# AD9959.net
KiCad netlist of a schematic drawn in Altium Designer
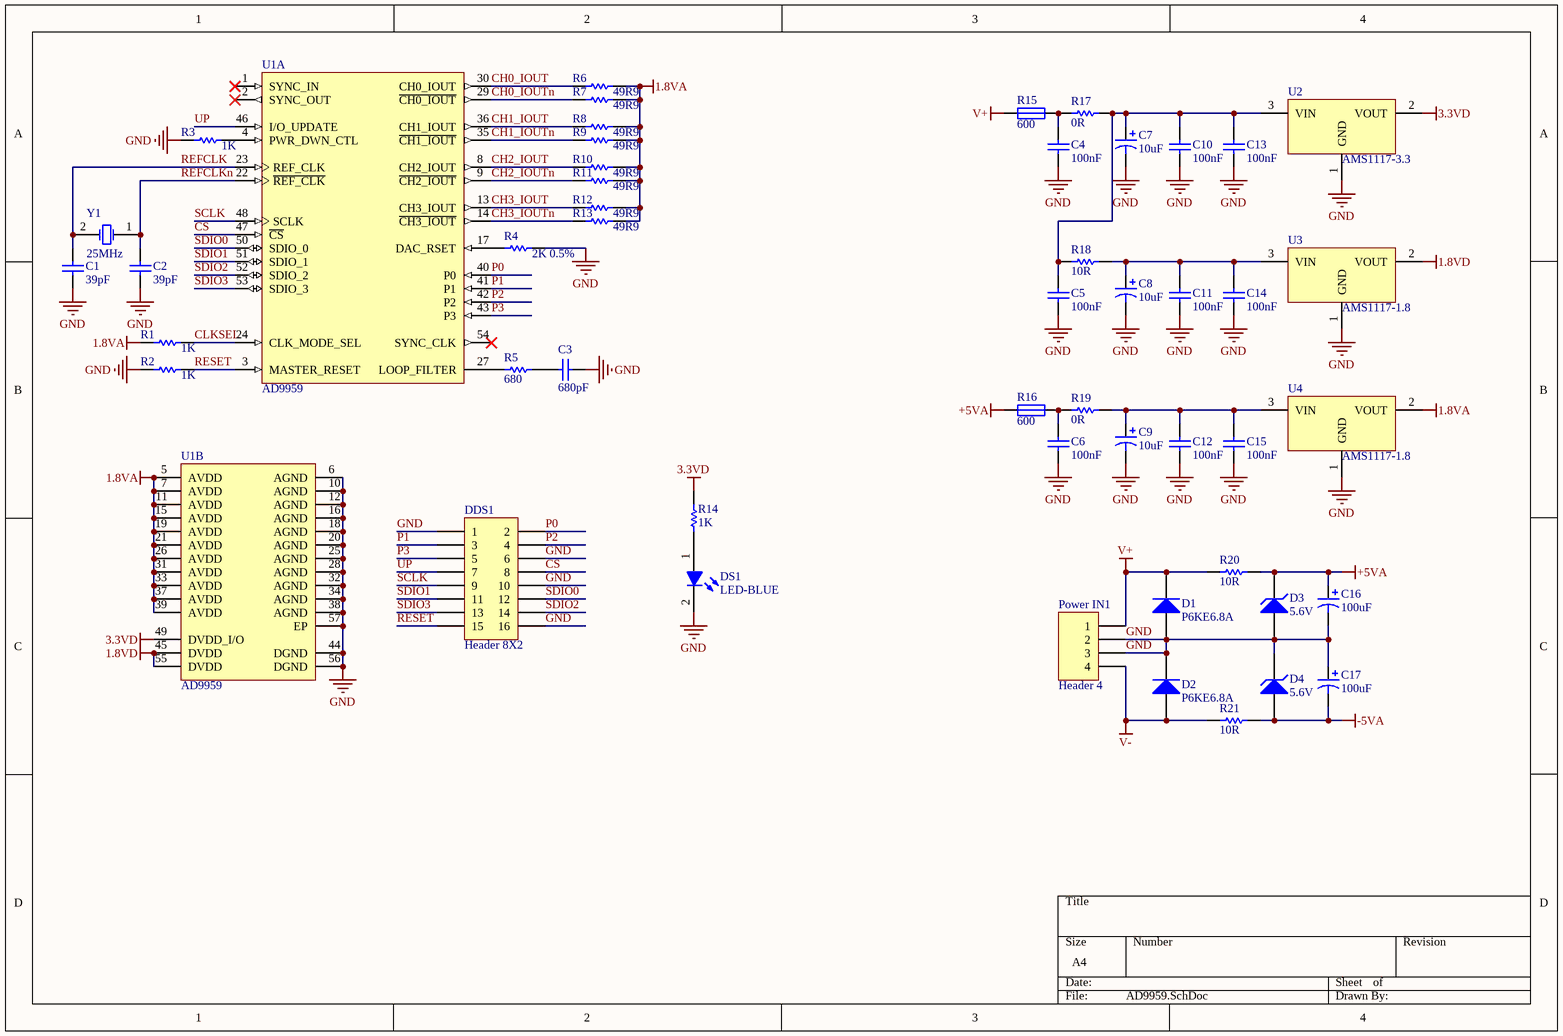
[diagram p0: AD9959.SchDoc]

(export (version "E")
  (design (tool "Eeschema 10.0.6"))
  (components
    (comp (ref "C1")
      (value "39pF")
      (footprint "CAPC0603(1608)55_M")
      (libsource (lib "Slivy's ibrary") (part "CAP"))
    )
    (comp (ref "C2")
      (value "39pF")
      (footprint "CAPC0603(1608)55_M")
      (libsource (lib "Slivy's ibrary") (part "CAP"))
    )
    (comp (ref "C3")
      (value "680pF")
      (footprint "CAPC0603(1608)55_M")
      (libsource (lib "Slivy's ibrary") (part "CAP"))
    )
    (comp (ref "C4")
      (value "100nF")
      (footprint "CAPC0603(1608)55_M")
      (libsource (lib "Slivy's ibrary") (part "CAP"))
    )
    (comp (ref "C5")
      (value "100nF")
      (footprint "CAPC0603(1608)55_M")
      (libsource (lib "Slivy's ibrary") (part "CAP"))
    )
    (comp (ref "C6")
      (value "100nF")
      (footprint "CAPC0603(1608)55_M")
      (libsource (lib "Slivy's ibrary") (part "CAP"))
    )
    (comp (ref "C7")
      (value "10uF")
      (footprint "CAPC3528")
      (libsource (lib "Slivy's ibrary") (part "CAP-Pol"))
    )
    (comp (ref "C8")
      (value "10uF")
      (footprint "CAPC3528")
      (libsource (lib "Slivy's ibrary") (part "CAP-Pol"))
    )
    (comp (ref "C9")
      (value "10uF")
      (footprint "CAPC3528")
      (libsource (lib "Slivy's ibrary") (part "CAP-Pol"))
    )
    (comp (ref "C10")
      (value "100nF")
      (footprint "CAPC0603(1608)55_M")
      (libsource (lib "Slivy's ibrary") (part "CAP"))
    )
    (comp (ref "C11")
      (value "100nF")
      (footprint "CAPC0603(1608)55_M")
      (libsource (lib "Slivy's ibrary") (part "CAP"))
    )
    (comp (ref "C12")
      (value "100nF")
      (footprint "CAPC0603(1608)55_M")
      (libsource (lib "Slivy's ibrary") (part "CAP"))
    )
    (comp (ref "C13")
      (value "100nF")
      (footprint "CAPC0603(1608)55_M")
      (libsource (lib "Slivy's ibrary") (part "CAP"))
    )
    (comp (ref "C14")
      (value "100nF")
      (footprint "CAPC0603(1608)55_M")
      (libsource (lib "Slivy's ibrary") (part "CAP"))
    )
    (comp (ref "C15")
      (value "100nF")
      (footprint "CAPC0603(1608)55_M")
      (libsource (lib "Slivy's ibrary") (part "CAP"))
    )
    (comp (ref "C16")
      (value "100uF")
      (footprint "CAPC7343")
      (libsource (lib "Slivy's ibrary") (part "CAP-Pol"))
    )
    (comp (ref "C17")
      (value "100uF")
      (footprint "CAPC7343")
      (libsource (lib "Slivy's ibrary") (part "CAP-Pol"))
    )
    (comp (ref "D1")
      (value "P6KE6.8A")
      (footprint "DO-214AC")
      (libsource (lib "Slivy's ibrary") (part "Diode"))
    )
    (comp (ref "D2")
      (value "P6KE6.8A")
      (footprint "DO-214AC")
      (libsource (lib "Slivy's ibrary") (part "Diode"))
    )
    (comp (ref "D3")
      (value "5.6V")
      (footprint "LL34")
      (description "Zener Diode")
      (fields (field (name "PUBLISHER") "Altium Limited"))
      (libsource (lib "Miscellaneous Devices") (part "D Zener"))
    )
    (comp (ref "D4")
      (value "5.6V")
      (footprint "LL34")
      (description "Zener Diode")
      (fields (field (name "PUBLISHER") "Altium Limited"))
      (libsource (lib "Miscellaneous Devices") (part "D Zener"))
    )
    (comp (ref "DDS1")
      (value "Header 8X2")
      (footprint "HEADER8X2")
      (description "Header, 8-Pin, Dual row")
      (fields (field (name "PUBLISHER") "Altium Limited"))
      (libsource (lib "Miscellaneous Connectors") (part "Header 8X2"))
    )
    (comp (ref "DS1")
      (value "LED-BLUE")
      (footprint "0603LED_BLUE_V")
      (libsource (lib "Slivy's ibrary") (part "LED-BLUE"))
    )
    (comp (ref "Power IN1")
      (value "Header 4")
      (footprint "3.96-4")
      (description "Header, 4-Pin")
      (fields (field (name "PUBLISHER") "Altium Limited"))
      (libsource (lib "Miscellaneous Connectors") (part "Header 4"))
    )
    (comp (ref "R1")
      (value "1K")
      (footprint "RESC0603(1608)_M")
      (libsource (lib "Slivy's ibrary") (part "RES"))
    )
    (comp (ref "R2")
      (value "1K")
      (footprint "RESC0603(1608)_M")
      (libsource (lib "Slivy's ibrary") (part "RES"))
    )
    (comp (ref "R3")
      (value "1K")
      (footprint "RESC0603(1608)_M")
      (libsource (lib "Slivy's ibrary") (part "RES"))
    )
    (comp (ref "R4")
      (value "2K 0.5%")
      (footprint "RESC0603(1608)_M")
      (libsource (lib "Slivy's ibrary") (part "RES"))
    )
    (comp (ref "R5")
      (value "680")
      (footprint "RESC0603(1608)_M")
      (libsource (lib "Slivy's ibrary") (part "RES"))
    )
    (comp (ref "R6")
      (value "49R9")
      (footprint "RESC0603(1608)_M")
      (libsource (lib "Slivy's ibrary") (part "RES"))
    )
    (comp (ref "R7")
      (value "49R9")
      (footprint "RESC0603(1608)_M")
      (libsource (lib "Slivy's ibrary") (part "RES"))
    )
    (comp (ref "R8")
      (value "49R9")
      (footprint "RESC0603(1608)_M")
      (libsource (lib "Slivy's ibrary") (part "RES"))
    )
    (comp (ref "R9")
      (value "49R9")
      (footprint "RESC0603(1608)_M")
      (libsource (lib "Slivy's ibrary") (part "RES"))
    )
    (comp (ref "R10")
      (value "49R9")
      (footprint "RESC0603(1608)_M")
      (libsource (lib "Slivy's ibrary") (part "RES"))
    )
    (comp (ref "R11")
      (value "49R9")
      (footprint "RESC0603(1608)_M")
      (libsource (lib "Slivy's ibrary") (part "RES"))
    )
    (comp (ref "R12")
      (value "49R9")
      (footprint "RESC0603(1608)_M")
      (libsource (lib "Slivy's ibrary") (part "RES"))
    )
    (comp (ref "R13")
      (value "49R9")
      (footprint "RESC0603(1608)_M")
      (libsource (lib "Slivy's ibrary") (part "RES"))
    )
    (comp (ref "R14")
      (value "1K")
      (footprint "RESC0603(1608)_M")
      (libsource (lib "Slivy's ibrary") (part "RES"))
    )
    (comp (ref "R15")
      (value "600")
      (footprint "SMD1206")
      (description "Ferrite Bead")
      (fields
        (field (name "MANUFACTURER") "Generic Components")
        (field (name "PUBLISHER") "Altium Hobart Technology Centre")
      )
      (libsource (lib "Integrated_Library1") (part "Ferrite Bead"))
    )
    (comp (ref "R16")
      (value "600")
      (footprint "SMD1206")
      (description "Ferrite Bead")
      (fields
        (field (name "MANUFACTURER") "Generic Components")
        (field (name "PUBLISHER") "Altium Hobart Technology Centre")
      )
      (libsource (lib "Integrated_Library1") (part "Ferrite Bead"))
    )
    (comp (ref "R17")
      (value "0R")
      (footprint "RESC0603(1608)_M")
      (libsource (lib "Slivy's ibrary") (part "RES"))
    )
    (comp (ref "R18")
      (value "10R")
      (footprint "RESC0603(1608)_M")
      (libsource (lib "Slivy's ibrary") (part "RES"))
    )
    (comp (ref "R19")
      (value "0R")
      (footprint "RESC0603(1608)_M")
      (libsource (lib "Slivy's ibrary") (part "RES"))
    )
    (comp (ref "R20")
      (value "10R")
      (footprint "RESC0603(1608)_M")
      (libsource (lib "Slivy's ibrary") (part "RES"))
    )
    (comp (ref "R21")
      (value "10R")
      (footprint "RESC0603(1608)_M")
      (libsource (lib "Slivy's ibrary") (part "RES"))
    )
    (comp (ref "U1") (value "AD9959") (footprint "QFN56") (libsource (lib "Slivy's ibrary") (part "AD9959")))
    (comp (ref "U2")
      (value "AMS1117-3.3")
      (footprint "SOT-223_M")
      (libsource (lib "Slivy's ibrary") (part "AMS1117"))
    )
    (comp (ref "U3")
      (value "AMS1117-1.8")
      (footprint "SOT-223_M")
      (libsource (lib "Slivy's ibrary") (part "AMS1117"))
    )
    (comp (ref "U4")
      (value "AMS1117-1.8")
      (footprint "SOT-223_M")
      (libsource (lib "Slivy's ibrary") (part "AMS1117"))
    )
    (comp (ref "Y1")
      (value "25MHz")
      (footprint "HC-49S")
      (description "Crystal Oscillator")
      (fields (field (name "PUBLISHER") "Altium Limited"))
      (libsource (lib "Slivy's ibrary") (part "XTAL"))
    )
  )
  (nets
    (net (code "1") (name "+5VA") (class "Default")
      (node (ref "C16") (pin "1") (pinfunction "1_1") (pintype "passive"))
      (node (ref "D3") (pin "2") (pinfunction "K_2") (pintype "passive"))
      (node (ref "R16") (pin "1") (pinfunction "1_1") (pintype "passive"))
      (node (ref "R20") (pin "2") (pinfunction "2_2") (pintype "passive"))
    )
    (net (code "2") (name "-5VA") (class "Default")
      (node (ref "C17") (pin "2") (pinfunction "2_2") (pintype "passive"))
      (node (ref "D4") (pin "1") (pinfunction "A_1") (pintype "passive"))
      (node (ref "R21") (pin "2") (pinfunction "2_2") (pintype "passive"))
    )
    (net (code "3") (name "/CH0_IOUT") (class "Default")
      (node (ref "R6") (pin "1") (pinfunction "1_1") (pintype "passive"))
      (node (ref "U1") (pin "30") (pinfunction "CH0_IOUT_30") (pintype "output"))
    )
    (net (code "4") (name "/CH0_IOUTn") (class "Default")
      (node (ref "R7") (pin "1") (pinfunction "1_1") (pintype "passive"))
      (node (ref "U1") (pin "29") (pinfunction "~{CH0_IOUT}_29") (pintype "output"))
    )
    (net (code "5") (name "/CH1_IOUT") (class "Default")
      (node (ref "R8") (pin "1") (pinfunction "1_1") (pintype "passive"))
      (node (ref "U1") (pin "36") (pinfunction "CH1_IOUT_36") (pintype "output"))
    )
    (net (code "6") (name "/CH1_IOUTn") (class "Default")
      (node (ref "R9") (pin "1") (pinfunction "1_1") (pintype "passive"))
      (node (ref "U1") (pin "35") (pinfunction "~{CH1_IOUT}_35") (pintype "output"))
    )
    (net (code "7") (name "/CH2_IOUT") (class "Default")
      (node (ref "R10") (pin "1") (pinfunction "1_1") (pintype "passive"))
      (node (ref "U1") (pin "8") (pinfunction "CH2_IOUT_8") (pintype "output"))
    )
    (net (code "8") (name "/CH2_IOUTn") (class "Default")
      (node (ref "R11") (pin "1") (pinfunction "1_1") (pintype "passive"))
      (node (ref "U1") (pin "9") (pinfunction "~{CH2_IOUT}_9") (pintype "output"))
    )
    (net (code "9") (name "/CH3_IOUT") (class "Default")
      (node (ref "R12") (pin "1") (pinfunction "1_1") (pintype "passive"))
      (node (ref "U1") (pin "13") (pinfunction "CH3_IOUT_13") (pintype "output"))
    )
    (net (code "10") (name "/CH3_IOUTn") (class "Default")
      (node (ref "R13") (pin "1") (pinfunction "1_1") (pintype "passive"))
      (node (ref "U1") (pin "14") (pinfunction "~{CH3_IOUT}_14") (pintype "output"))
    )
    (net (code "11") (name "/CLKSEL") (class "Default")
      (node (ref "R1") (pin "2") (pinfunction "2_2") (pintype "passive"))
      (node (ref "U1") (pin "24") (pinfunction "CLK_MODE_SEL_24") (pintype "input"))
    )
    (net (code "12") (name "/CS") (class "Default")
      (node (ref "DDS1") (pin "8") (pinfunction "8_8") (pintype "passive"))
      (node (ref "U1") (pin "47") (pinfunction "~{CS}_47") (pintype "input"))
    )
    (net (code "13") (name "/P0") (class "Default")
      (node (ref "DDS1") (pin "2") (pinfunction "2_2") (pintype "passive"))
      (node (ref "U1") (pin "40") (pinfunction "P0_40") (pintype "input"))
    )
    (net (code "14") (name "/P1") (class "Default")
      (node (ref "DDS1") (pin "3") (pinfunction "3_3") (pintype "passive"))
      (node (ref "U1") (pin "41") (pinfunction "P1_41") (pintype "input"))
    )
    (net (code "15") (name "/P2") (class "Default")
      (node (ref "DDS1") (pin "4") (pinfunction "4_4") (pintype "passive"))
      (node (ref "U1") (pin "42") (pinfunction "P2_42") (pintype "input"))
    )
    (net (code "16") (name "/P3") (class "Default")
      (node (ref "DDS1") (pin "5") (pinfunction "5_5") (pintype "passive"))
      (node (ref "U1") (pin "43") (pinfunction "P3_43") (pintype "input"))
    )
    (net (code "17") (name "/REFCLK") (class "Default")
      (node (ref "C1") (pin "2") (pinfunction "2_2") (pintype "passive"))
      (node (ref "U1") (pin "23") (pinfunction "REF_CLK_23") (pintype "input"))
      (node (ref "Y1") (pin "2") (pinfunction "OSC2_2") (pintype "passive"))
    )
    (net (code "18") (name "/REFCLKn") (class "Default")
      (node (ref "C2") (pin "2") (pinfunction "2_2") (pintype "passive"))
      (node (ref "U1") (pin "22") (pinfunction "~{REF_CLK}_22") (pintype "input"))
      (node (ref "Y1") (pin "1") (pinfunction "OSC1_1") (pintype "passive"))
    )
    (net (code "19") (name "/RESET") (class "Default")
      (node (ref "DDS1") (pin "15") (pinfunction "15_15") (pintype "passive"))
      (node (ref "R2") (pin "2") (pinfunction "2_2") (pintype "passive"))
      (node (ref "U1") (pin "3") (pinfunction "MASTER_RESET_3") (pintype "input"))
    )
    (net (code "20") (name "/SCLK") (class "Default")
      (node (ref "DDS1") (pin "9") (pinfunction "9_9") (pintype "passive"))
      (node (ref "U1") (pin "48") (pinfunction "SCLK_48") (pintype "input"))
    )
    (net (code "21") (name "/SDIO0") (class "Default")
      (node (ref "DDS1") (pin "12") (pinfunction "12_12") (pintype "passive"))
      (node (ref "U1") (pin "50") (pinfunction "SDIO_0_50") (pintype "bidirectional"))
    )
    (net (code "22") (name "/SDIO1") (class "Default")
      (node (ref "DDS1") (pin "11") (pinfunction "11_11") (pintype "passive"))
      (node (ref "U1") (pin "51") (pinfunction "SDIO_1_51") (pintype "bidirectional"))
    )
    (net (code "23") (name "/SDIO2") (class "Default")
      (node (ref "DDS1") (pin "14") (pinfunction "14_14") (pintype "passive"))
      (node (ref "U1") (pin "52") (pinfunction "SDIO_2_52") (pintype "bidirectional"))
    )
    (net (code "24") (name "/SDIO3") (class "Default")
      (node (ref "DDS1") (pin "13") (pinfunction "13_13") (pintype "passive"))
      (node (ref "U1") (pin "53") (pinfunction "SDIO_3_53") (pintype "bidirectional"))
    )
    (net (code "25") (name "/UP") (class "Default")
      (node (ref "DDS1") (pin "7") (pinfunction "7_7") (pintype "passive"))
      (node (ref "U1") (pin "46") (pinfunction "I/O_UPDATE_46") (pintype "input"))
    )
    (net (code "26") (name "1.8VA") (class "Default")
      (node (ref "R1") (pin "1") (pinfunction "1_1") (pintype "passive"))
      (node (ref "R10") (pin "2") (pinfunction "2_2") (pintype "passive"))
      (node (ref "R11") (pin "2") (pinfunction "2_2") (pintype "passive"))
      (node (ref "R12") (pin "2") (pinfunction "2_2") (pintype "passive"))
      (node (ref "R13") (pin "2") (pinfunction "2_2") (pintype "passive"))
      (node (ref "R6") (pin "2") (pinfunction "2_2") (pintype "passive"))
      (node (ref "R7") (pin "2") (pinfunction "2_2") (pintype "passive"))
      (node (ref "R8") (pin "2") (pinfunction "2_2") (pintype "passive"))
      (node (ref "R9") (pin "2") (pinfunction "2_2") (pintype "passive"))
      (node (ref "U1") (pin "11") (pinfunction "AVDD_11") (pintype "power_in"))
      (node (ref "U1") (pin "15") (pinfunction "AVDD_15") (pintype "power_in"))
      (node (ref "U1") (pin "19") (pinfunction "AVDD_19") (pintype "power_in"))
      (node (ref "U1") (pin "21") (pinfunction "AVDD_21") (pintype "power_in"))
      (node (ref "U1") (pin "26") (pinfunction "AVDD_26") (pintype "power_in"))
      (node (ref "U1") (pin "31") (pinfunction "AVDD_31") (pintype "power_in"))
      (node (ref "U1") (pin "33") (pinfunction "AVDD_33") (pintype "power_in"))
      (node (ref "U1") (pin "37") (pinfunction "AVDD_37") (pintype "power_in"))
      (node (ref "U1") (pin "39") (pinfunction "AVDD_39") (pintype "power_in"))
      (node (ref "U1") (pin "5") (pinfunction "AVDD_5") (pintype "power_in"))
      (node (ref "U1") (pin "7") (pinfunction "AVDD_7") (pintype "power_in"))
      (node (ref "U4") (pin "2") (pinfunction "VOUT_2") (pintype "power_in"))
    )
    (net (code "27") (name "1.8VD") (class "Default")
      (node (ref "U1") (pin "45") (pinfunction "DVDD_45") (pintype "power_in"))
      (node (ref "U1") (pin "55") (pinfunction "DVDD_55") (pintype "power_in"))
      (node (ref "U3") (pin "2") (pinfunction "VOUT_2") (pintype "power_in"))
    )
    (net (code "28") (name "3.3VD") (class "Default")
      (node (ref "R14") (pin "2") (pinfunction "2_2") (pintype "passive"))
      (node (ref "U1") (pin "49") (pinfunction "DVDD_I/O_49") (pintype "power_in"))
      (node (ref "U2") (pin "2") (pinfunction "VOUT_2") (pintype "power_in"))
    )
    (net (code "29") (name "GND") (class "Default")
      (node (ref "C1") (pin "1") (pinfunction "1_1") (pintype "passive"))
      (node (ref "C10") (pin "1") (pinfunction "1_1") (pintype "passive"))
      (node (ref "C11") (pin "1") (pinfunction "1_1") (pintype "passive"))
      (node (ref "C12") (pin "1") (pinfunction "1_1") (pintype "passive"))
      (node (ref "C13") (pin "1") (pinfunction "1_1") (pintype "passive"))
      (node (ref "C14") (pin "1") (pinfunction "1_1") (pintype "passive"))
      (node (ref "C15") (pin "1") (pinfunction "1_1") (pintype "passive"))
      (node (ref "C16") (pin "2") (pinfunction "2_2") (pintype "passive"))
      (node (ref "C17") (pin "1") (pinfunction "1_1") (pintype "passive"))
      (node (ref "C2") (pin "1") (pinfunction "1_1") (pintype "passive"))
      (node (ref "C3") (pin "2") (pinfunction "2_2") (pintype "passive"))
      (node (ref "C4") (pin "1") (pinfunction "1_1") (pintype "passive"))
      (node (ref "C5") (pin "1") (pinfunction "1_1") (pintype "passive"))
      (node (ref "C6") (pin "1") (pinfunction "1_1") (pintype "passive"))
      (node (ref "C7") (pin "2") (pinfunction "2_2") (pintype "passive"))
      (node (ref "C8") (pin "2") (pinfunction "2_2") (pintype "passive"))
      (node (ref "C9") (pin "2") (pinfunction "2_2") (pintype "passive"))
      (node (ref "D1") (pin "2") (pinfunction "A_2") (pintype "passive"))
      (node (ref "D2") (pin "1") (pinfunction "K_1") (pintype "passive"))
      (node (ref "D3") (pin "1") (pinfunction "A_1") (pintype "passive"))
      (node (ref "D4") (pin "2") (pinfunction "K_2") (pintype "passive"))
      (node (ref "DDS1") (pin "1") (pinfunction "1_1") (pintype "passive"))
      (node (ref "DDS1") (pin "10") (pinfunction "10_10") (pintype "passive"))
      (node (ref "DDS1") (pin "16") (pinfunction "16_16") (pintype "passive"))
      (node (ref "DDS1") (pin "6") (pinfunction "6_6") (pintype "passive"))
      (node (ref "DS1") (pin "2") (pinfunction "K_2") (pintype "passive"))
      (node (ref "Power IN1") (pin "2") (pinfunction "2_2") (pintype "passive"))
      (node (ref "Power IN1") (pin "3") (pinfunction "3_3") (pintype "passive"))
      (node (ref "R2") (pin "1") (pinfunction "1_1") (pintype "passive"))
      (node (ref "R3") (pin "1") (pinfunction "1_1") (pintype "passive"))
      (node (ref "R4") (pin "2") (pinfunction "2_2") (pintype "passive"))
      (node (ref "U1") (pin "10") (pinfunction "AGND_10") (pintype "power_in"))
      (node (ref "U1") (pin "12") (pinfunction "AGND_12") (pintype "power_in"))
      (node (ref "U1") (pin "16") (pinfunction "AGND_16") (pintype "power_in"))
      (node (ref "U1") (pin "18") (pinfunction "AGND_18") (pintype "power_in"))
      (node (ref "U1") (pin "20") (pinfunction "AGND_20") (pintype "power_in"))
      (node (ref "U1") (pin "25") (pinfunction "AGND_25") (pintype "power_in"))
      (node (ref "U1") (pin "28") (pinfunction "AGND_28") (pintype "power_in"))
      (node (ref "U1") (pin "32") (pinfunction "AGND_32") (pintype "power_in"))
      (node (ref "U1") (pin "34") (pinfunction "AGND_34") (pintype "power_in"))
      (node (ref "U1") (pin "38") (pinfunction "AGND_38") (pintype "power_in"))
      (node (ref "U1") (pin "44") (pinfunction "DGND_44") (pintype "power_in"))
      (node (ref "U1") (pin "56") (pinfunction "DGND_56") (pintype "power_in"))
      (node (ref "U1") (pin "57") (pinfunction "EP_57") (pintype "power_in"))
      (node (ref "U1") (pin "6") (pinfunction "AGND_6") (pintype "power_in"))
      (node (ref "U2") (pin "1") (pinfunction "GND_1") (pintype "power_in"))
      (node (ref "U3") (pin "1") (pinfunction "GND_1") (pintype "power_in"))
      (node (ref "U4") (pin "1") (pinfunction "GND_1") (pintype "power_in"))
    )
    (net (code "30") (name "Net-(C3-Pad1)") (class "Default")
      (node (ref "C3") (pin "1") (pinfunction "1_1") (pintype "passive"))
      (node (ref "R5") (pin "2") (pinfunction "2_2") (pintype "passive"))
    )
    (net (code "31") (name "Net-(C4-Pad2)") (class "Default")
      (node (ref "C4") (pin "2") (pinfunction "2_2") (pintype "passive"))
      (node (ref "R15") (pin "2") (pinfunction "2_2") (pintype "passive"))
      (node (ref "R17") (pin "1") (pinfunction "1_1") (pintype "passive"))
    )
    (net (code "32") (name "Net-(C6-Pad2)") (class "Default")
      (node (ref "C6") (pin "2") (pinfunction "2_2") (pintype "passive"))
      (node (ref "R16") (pin "2") (pinfunction "2_2") (pintype "passive"))
      (node (ref "R19") (pin "1") (pinfunction "1_1") (pintype "passive"))
    )
    (net (code "33") (name "Net-(DS1-A)") (class "Default")
      (node (ref "DS1") (pin "1") (pinfunction "A_1") (pintype "passive"))
      (node (ref "R14") (pin "1") (pinfunction "1_1") (pintype "passive"))
    )
    (net (code "34") (name "Net-(U1A-DAC_RSET)") (class "Default")
      (node (ref "R4") (pin "1") (pinfunction "1_1") (pintype "passive"))
      (node (ref "U1") (pin "17") (pinfunction "DAC_RSET_17") (pintype "input"))
    )
    (net (code "35") (name "Net-(U1A-LOOP_FILTER)") (class "Default")
      (node (ref "R5") (pin "1") (pinfunction "1_1") (pintype "passive"))
      (node (ref "U1") (pin "27") (pinfunction "LOOP_FILTER_27") (pintype "passive"))
    )
    (net (code "36") (name "Net-(U1A-PWR_DWN_CTL)") (class "Default")
      (node (ref "R3") (pin "2") (pinfunction "2_2") (pintype "passive"))
      (node (ref "U1") (pin "4") (pinfunction "PWR_DWN_CTL_4") (pintype "input"))
    )
    (net (code "37") (name "Net-(U2-VIN)") (class "Default")
      (node (ref "C10") (pin "2") (pinfunction "2_2") (pintype "passive"))
      (node (ref "C13") (pin "2") (pinfunction "2_2") (pintype "passive"))
      (node (ref "C5") (pin "2") (pinfunction "2_2") (pintype "passive"))
      (node (ref "C7") (pin "1") (pinfunction "1_1") (pintype "passive"))
      (node (ref "R17") (pin "2") (pinfunction "2_2") (pintype "passive"))
      (node (ref "R18") (pin "1") (pinfunction "1_1") (pintype "passive"))
      (node (ref "U2") (pin "3") (pinfunction "VIN_3") (pintype "power_in"))
    )
    (net (code "38") (name "Net-(U3-VIN)") (class "Default")
      (node (ref "C11") (pin "2") (pinfunction "2_2") (pintype "passive"))
      (node (ref "C14") (pin "2") (pinfunction "2_2") (pintype "passive"))
      (node (ref "C8") (pin "1") (pinfunction "1_1") (pintype "passive"))
      (node (ref "R18") (pin "2") (pinfunction "2_2") (pintype "passive"))
      (node (ref "U3") (pin "3") (pinfunction "VIN_3") (pintype "power_in"))
    )
    (net (code "39") (name "Net-(U4-VIN)") (class "Default")
      (node (ref "C12") (pin "2") (pinfunction "2_2") (pintype "passive"))
      (node (ref "C15") (pin "2") (pinfunction "2_2") (pintype "passive"))
      (node (ref "C9") (pin "1") (pinfunction "1_1") (pintype "passive"))
      (node (ref "R19") (pin "2") (pinfunction "2_2") (pintype "passive"))
      (node (ref "U4") (pin "3") (pinfunction "VIN_3") (pintype "power_in"))
    )
    (net (code "40") (name "V+") (class "Default")
      (node (ref "D1") (pin "1") (pinfunction "K_1") (pintype "passive"))
      (node (ref "Power IN1") (pin "1") (pinfunction "1_1") (pintype "passive"))
      (node (ref "R15") (pin "1") (pinfunction "1_1") (pintype "passive"))
      (node (ref "R20") (pin "1") (pinfunction "1_1") (pintype "passive"))
    )
    (net (code "41") (name "V-") (class "Default")
      (node (ref "D2") (pin "2") (pinfunction "A_2") (pintype "passive"))
      (node (ref "Power IN1") (pin "4") (pinfunction "4_4") (pintype "passive"))
      (node (ref "R21") (pin "1") (pinfunction "1_1") (pintype "passive"))
    )
    (net (code "42") (name "unconnected-(U1A-SYNC_CLK-Pad54)") (class "Default")
      (node (ref "U1") (pin "54") (pinfunction "SYNC_CLK_54") (pintype "output+no_connect"))
    )
    (net (code "43") (name "unconnected-(U1A-SYNC_IN-Pad1)") (class "Default")
      (node (ref "U1") (pin "1") (pinfunction "SYNC_IN_1") (pintype "input+no_connect"))
    )
    (net (code "44") (name "unconnected-(U1A-SYNC_OUT-Pad2)") (class "Default")
      (node (ref "U1") (pin "2") (pinfunction "SYNC_OUT_2") (pintype "output+no_connect"))
    )
  )
)
